# Mezzanine_GPIO_Breakout.net
KiCad netlist of a schematic drawn in EAGLE
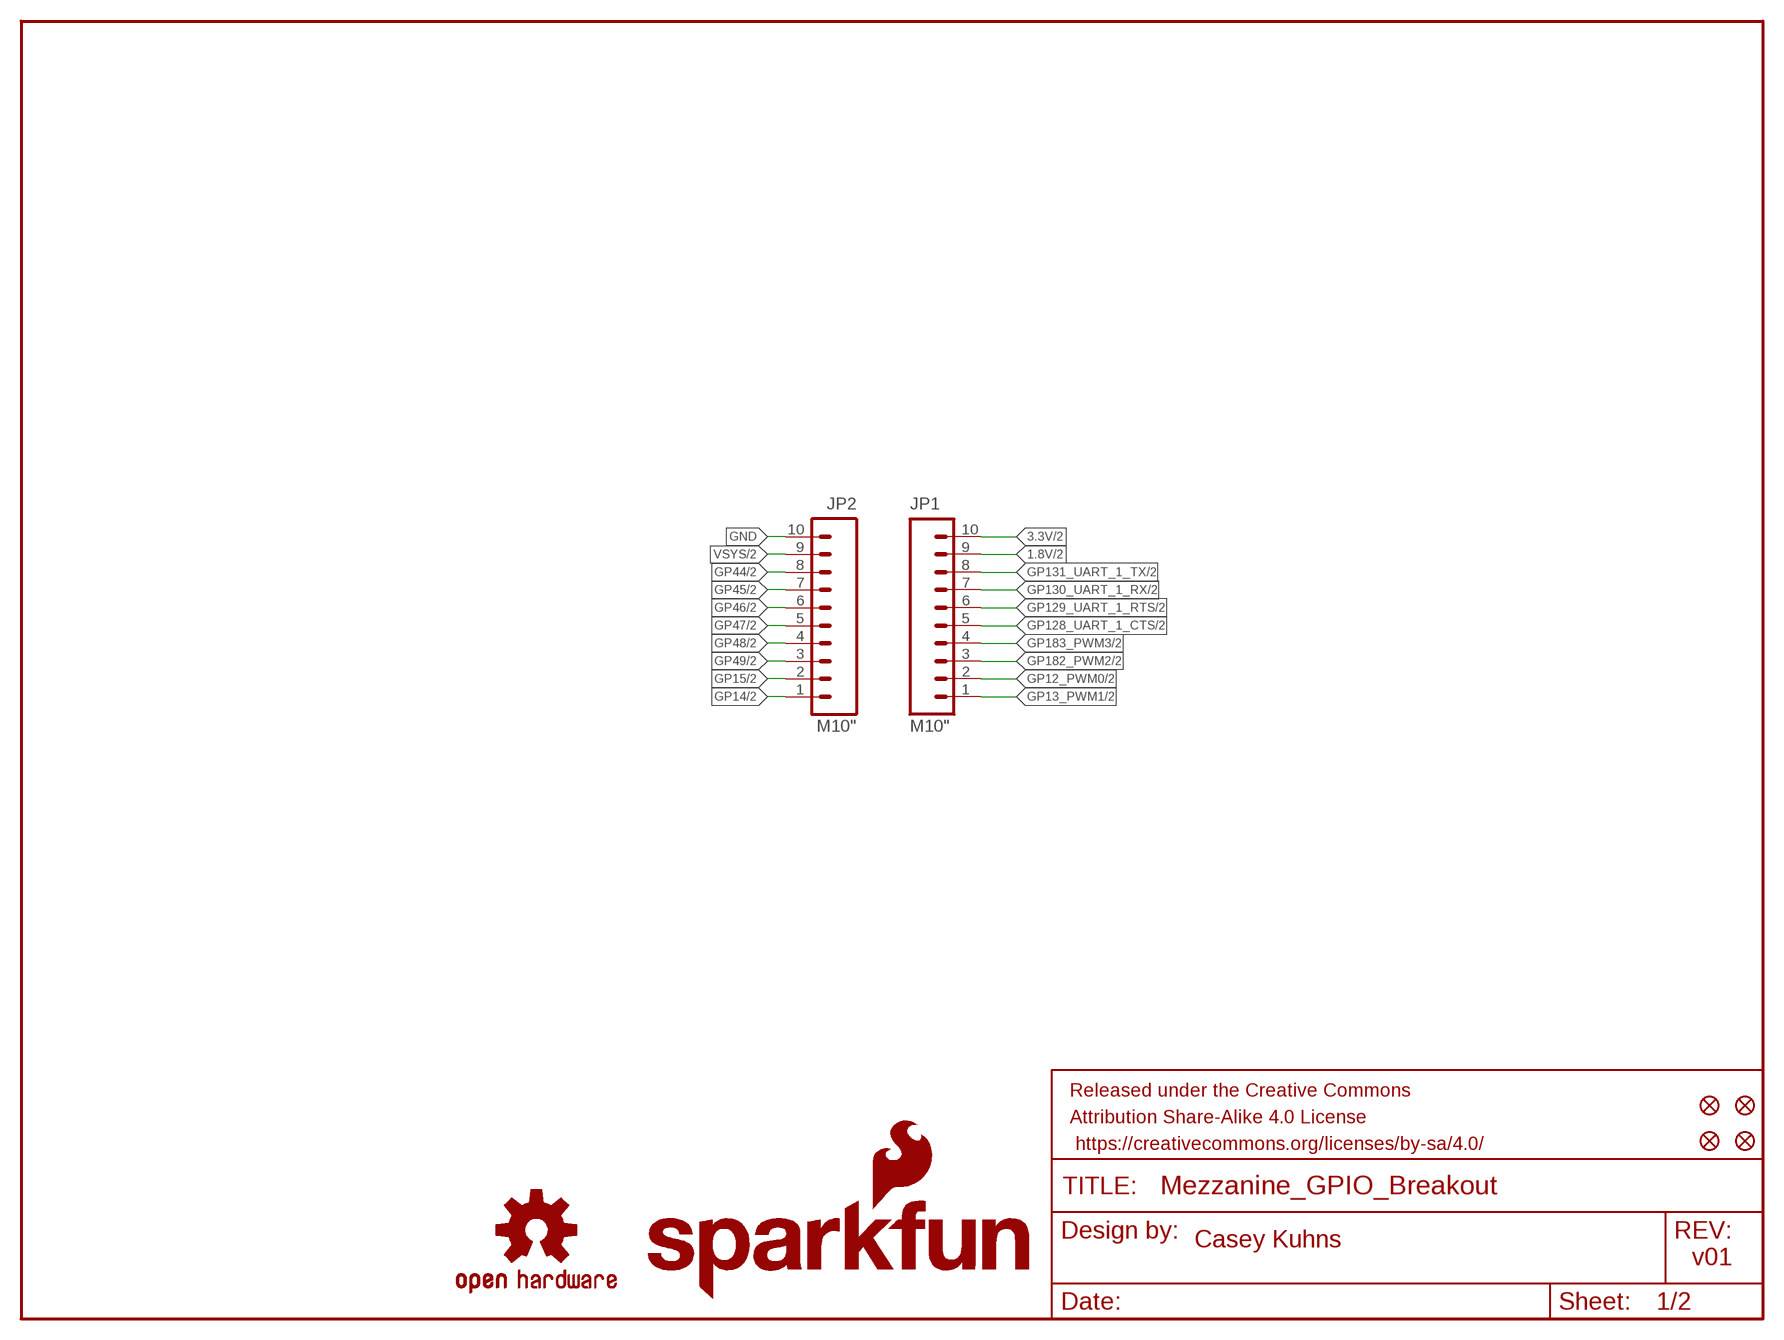
[diagram p0: schematic, sheet 1]
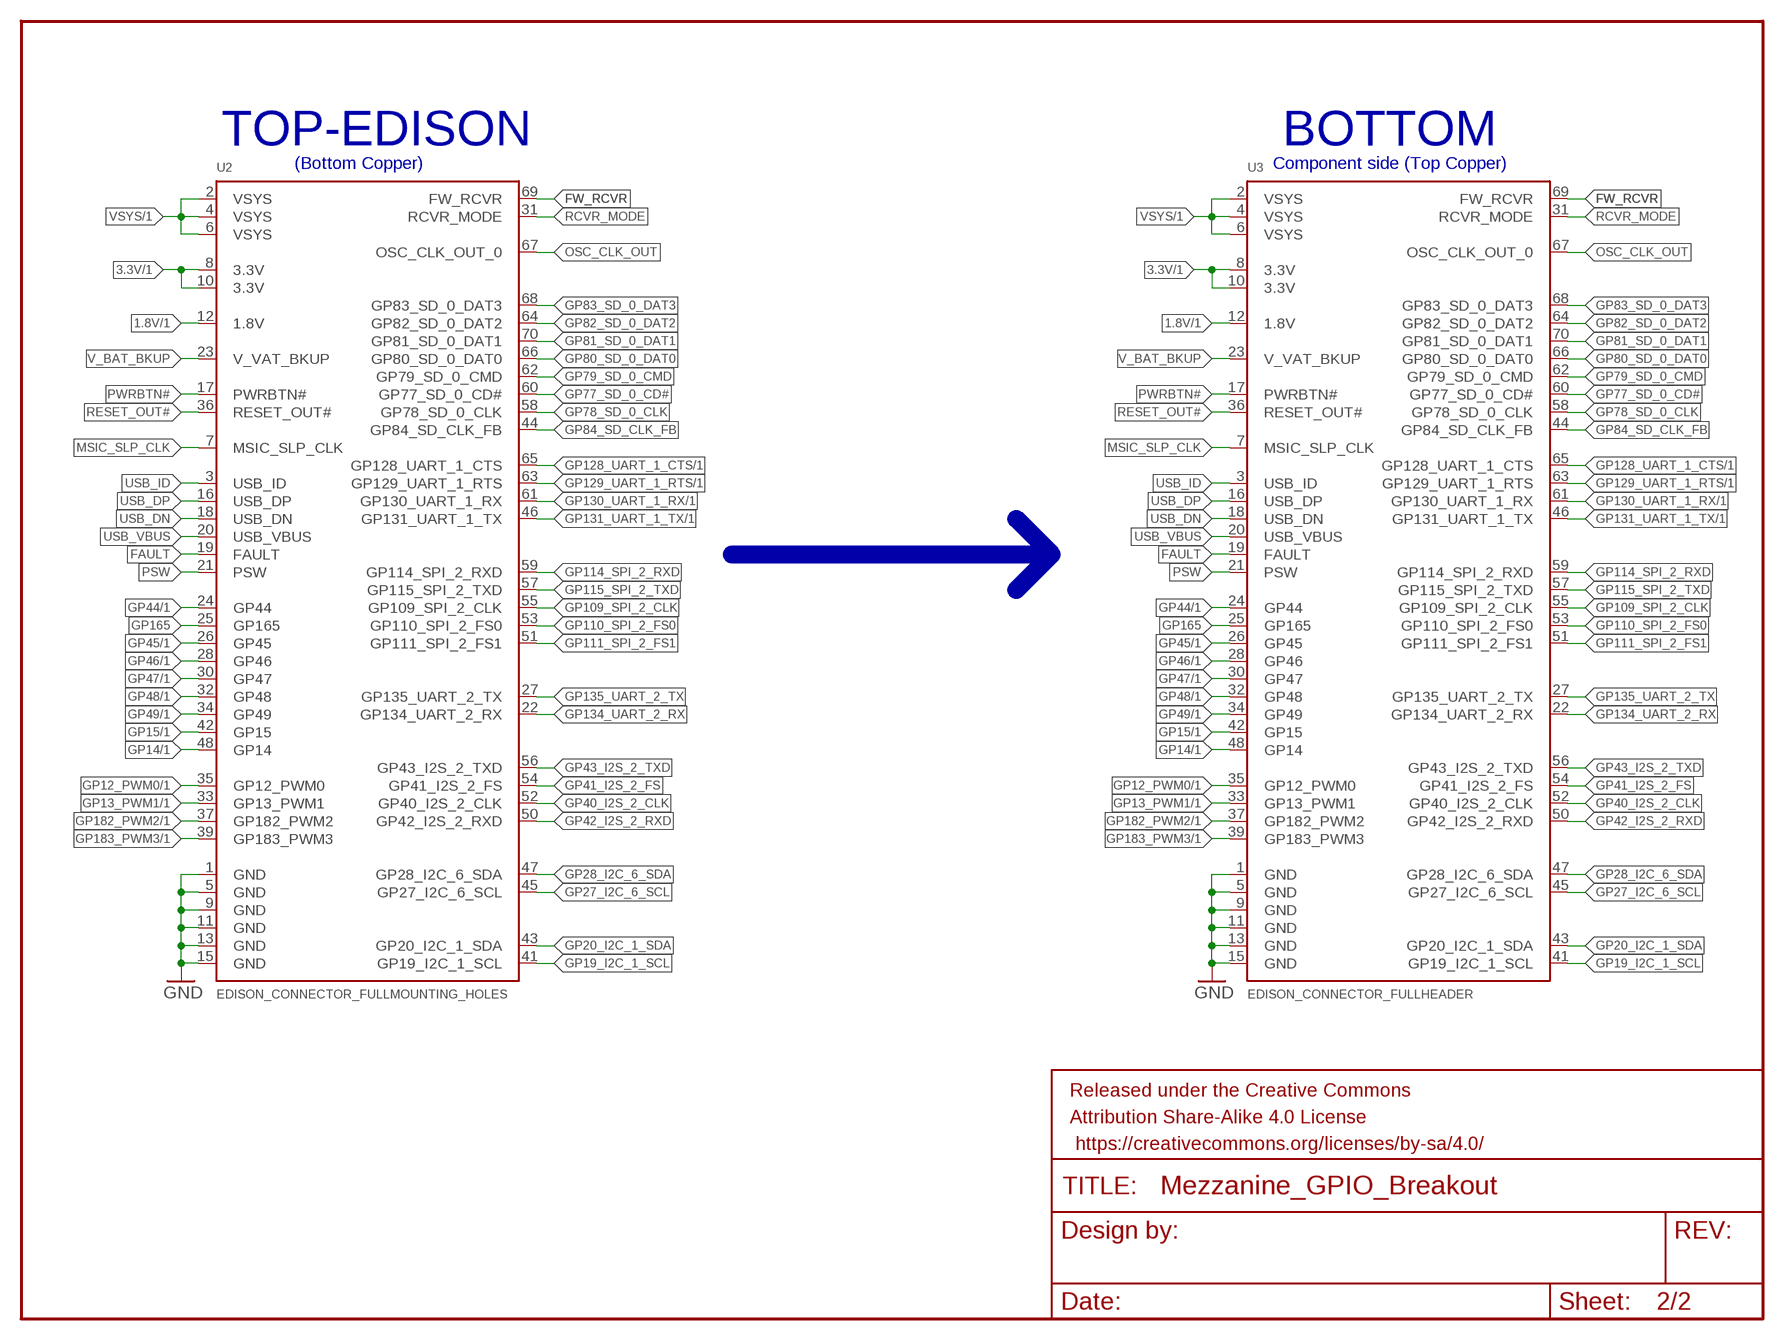
[diagram p1: schematic, sheet 2]

(export (version "E")
  (design (tool "Eeschema 10.0.6"))
  (components
    (comp (ref "FRAME2")
      (value "FRAME-LETTER")
      (footprint "eagle-import:CREATIVE_COMMONS")
      (libsource (lib "eagle-import") (part "FRAME-LETTER"))
    )
    (comp (ref "U2")
      (value "EDISON_CONNECTOR_FULLMOUNTING_HOLES")
      (footprint "eagle-import:EDISON_DAUGHTER")
      (libsource (lib "eagle-import") (part "EDISON_CONNECTOR_FULLMOUNTING_HOLES"))
    )
    (comp (ref "U3")
      (value "EDISON_CONNECTOR_FULLHEADER")
      (footprint "eagle-import:DF40C-70DP-0.4(51)")
      (libsource (lib "eagle-import") (part "EDISON_CONNECTOR_FULLHEADER"))
    )
    (comp (ref "FID1")
      (value "FIDUCIAL1X2")
      (footprint "eagle-import:FIDUCIAL-1X2")
      (libsource (lib "eagle-import") (part "FIDUCIAL1X2"))
    )
    (comp (ref "FID2")
      (value "FIDUCIAL1X2")
      (footprint "eagle-import:FIDUCIAL-1X2")
      (libsource (lib "eagle-import") (part "FIDUCIAL1X2"))
    )
    (comp (ref "FID3")
      (value "FIDUCIAL1X2")
      (footprint "eagle-import:FIDUCIAL-1X2")
      (libsource (lib "eagle-import") (part "FIDUCIAL1X2"))
    )
    (comp (ref "FID4")
      (value "FIDUCIAL1X2")
      (footprint "eagle-import:FIDUCIAL-1X2")
      (libsource (lib "eagle-import") (part "FIDUCIAL1X2"))
    )
    (comp (ref "FRAME1")
      (value "FRAME-LETTER")
      (footprint "eagle-import:CREATIVE_COMMONS")
      (libsource (lib "eagle-import") (part "FRAME-LETTER"))
    )
    (comp (ref "JP1")
      (value "M10\"")
      (footprint "eagle-import:1X10")
      (libsource (lib "eagle-import") (part "M10{dblquote}"))
    )
    (comp (ref "JP2")
      (value "M10\"")
      (footprint "eagle-import:1X10")
      (libsource (lib "eagle-import") (part "M10{dblquote}"))
    )
    (comp (ref "LOGO1")
      (value "OSHW-LOGOS")
      (footprint "eagle-import:OSHW-LOGO-S")
      (libsource (lib "eagle-import") (part "OSHW-LOGOS"))
    )
    (comp (ref "LOGO4")
      (value "SFE_LOGO_NAME_FLAME.1_INCH")
      (footprint "eagle-import:SFE_LOGO_NAME_FLAME_.1")
      (libsource (lib "eagle-import") (part "SFE_LOGO_NAME_FLAME.1_INCH"))
    )
  )
  (nets
    (net (code "1") (name "1.8V") (class "Default")
      (node (ref "JP1") (pin "9") (pinfunction "9_9") (pintype "passive"))
      (node (ref "U2") (pin "12") (pinfunction "1.8V_12") (pintype "bidirectional"))
      (node (ref "U3") (pin "12") (pinfunction "1.8V_12") (pintype "bidirectional"))
    )
    (net (code "2") (name "3.3V") (class "Default")
      (node (ref "JP1") (pin "10") (pinfunction "10_10") (pintype "passive"))
      (node (ref "U2") (pin "10") (pinfunction "3.3V_10") (pintype "bidirectional"))
      (node (ref "U2") (pin "8") (pinfunction "3.3V_8") (pintype "bidirectional"))
      (node (ref "U3") (pin "10") (pinfunction "3.3V_10") (pintype "bidirectional"))
      (node (ref "U3") (pin "8") (pinfunction "3.3V_8") (pintype "bidirectional"))
    )
    (net (code "3") (name "FAULT") (class "Default")
      (node (ref "U2") (pin "19") (pinfunction "FAULT_19") (pintype "bidirectional"))
      (node (ref "U3") (pin "19") (pinfunction "FAULT_19") (pintype "bidirectional"))
    )
    (net (code "4") (name "FW_RCVR") (class "Default")
      (node (ref "U2") (pin "69") (pinfunction "FW_RCVR_69") (pintype "bidirectional"))
      (node (ref "U3") (pin "69") (pinfunction "FW_RCVR_69") (pintype "bidirectional"))
    )
    (net (code "5") (name "GND") (class "Default")
      (node (ref "JP2") (pin "10") (pinfunction "10_10") (pintype "passive"))
      (node (ref "U2") (pin "1") (pinfunction "GND_1") (pintype "bidirectional"))
      (node (ref "U2") (pin "11") (pinfunction "GND_11") (pintype "bidirectional"))
      (node (ref "U2") (pin "13") (pinfunction "GND_13") (pintype "bidirectional"))
      (node (ref "U2") (pin "15") (pinfunction "GND_15") (pintype "bidirectional"))
      (node (ref "U2") (pin "5") (pinfunction "GND_5") (pintype "bidirectional"))
      (node (ref "U2") (pin "9") (pinfunction "GND_9") (pintype "bidirectional"))
      (node (ref "U3") (pin "1") (pinfunction "GND_1") (pintype "bidirectional"))
      (node (ref "U3") (pin "11") (pinfunction "GND_11") (pintype "bidirectional"))
      (node (ref "U3") (pin "13") (pinfunction "GND_13") (pintype "bidirectional"))
      (node (ref "U3") (pin "15") (pinfunction "GND_15") (pintype "bidirectional"))
      (node (ref "U3") (pin "5") (pinfunction "GND_5") (pintype "bidirectional"))
      (node (ref "U3") (pin "9") (pinfunction "GND_9") (pintype "bidirectional"))
    )
    (net (code "6") (name "GP12_PWM0") (class "Default")
      (node (ref "JP1") (pin "2") (pinfunction "2_2") (pintype "passive"))
      (node (ref "U2") (pin "35") (pinfunction "GP12_PWM0_35") (pintype "bidirectional"))
      (node (ref "U3") (pin "35") (pinfunction "GP12_PWM0_35") (pintype "bidirectional"))
    )
    (net (code "7") (name "GP13_PWM1") (class "Default")
      (node (ref "JP1") (pin "1") (pinfunction "1_1") (pintype "passive"))
      (node (ref "U2") (pin "33") (pinfunction "GP13_PWM1_33") (pintype "bidirectional"))
      (node (ref "U3") (pin "33") (pinfunction "GP13_PWM1_33") (pintype "bidirectional"))
    )
    (net (code "8") (name "GP14") (class "Default")
      (node (ref "JP2") (pin "1") (pinfunction "1_1") (pintype "passive"))
      (node (ref "U2") (pin "48") (pinfunction "GP14_48") (pintype "bidirectional"))
      (node (ref "U3") (pin "48") (pinfunction "GP14_48") (pintype "bidirectional"))
    )
    (net (code "9") (name "GP15") (class "Default")
      (node (ref "JP2") (pin "2") (pinfunction "2_2") (pintype "passive"))
      (node (ref "U2") (pin "42") (pinfunction "GP15_42") (pintype "bidirectional"))
      (node (ref "U3") (pin "42") (pinfunction "GP15_42") (pintype "bidirectional"))
    )
    (net (code "10") (name "GP19_I2C_1_SCL") (class "Default")
      (node (ref "U2") (pin "41") (pinfunction "GP19_I2C_1_SCL_41") (pintype "bidirectional"))
      (node (ref "U3") (pin "41") (pinfunction "GP19_I2C_1_SCL_41") (pintype "bidirectional"))
    )
    (net (code "11") (name "GP20_I2C_1_SDA") (class "Default")
      (node (ref "U2") (pin "43") (pinfunction "GP20_I2C_1_SDA_43") (pintype "bidirectional"))
      (node (ref "U3") (pin "43") (pinfunction "GP20_I2C_1_SDA_43") (pintype "bidirectional"))
    )
    (net (code "12") (name "GP27_I2C_6_SCL") (class "Default")
      (node (ref "U2") (pin "45") (pinfunction "GP27_I2C_6_SCL_45") (pintype "bidirectional"))
      (node (ref "U3") (pin "45") (pinfunction "GP27_I2C_6_SCL_45") (pintype "bidirectional"))
    )
    (net (code "13") (name "GP28_I2C_6_SDA") (class "Default")
      (node (ref "U2") (pin "47") (pinfunction "GP28_I2C_6_SDA_47") (pintype "bidirectional"))
      (node (ref "U3") (pin "47") (pinfunction "GP28_I2C_6_SDA_47") (pintype "bidirectional"))
    )
    (net (code "14") (name "GP40_I2S_2_CLK") (class "Default")
      (node (ref "U2") (pin "52") (pinfunction "GP40_I2S_2_CLK_52") (pintype "bidirectional"))
      (node (ref "U3") (pin "52") (pinfunction "GP40_I2S_2_CLK_52") (pintype "bidirectional"))
    )
    (net (code "15") (name "GP41_I2S_2_FS") (class "Default")
      (node (ref "U2") (pin "54") (pinfunction "GP41_I2S_2_FS_54") (pintype "bidirectional"))
      (node (ref "U3") (pin "54") (pinfunction "GP41_I2S_2_FS_54") (pintype "bidirectional"))
    )
    (net (code "16") (name "GP42_I2S_2_RXD") (class "Default")
      (node (ref "U2") (pin "50") (pinfunction "GP42_I2S_2_RXD_50") (pintype "bidirectional"))
      (node (ref "U3") (pin "50") (pinfunction "GP42_I2S_2_RXD_50") (pintype "bidirectional"))
    )
    (net (code "17") (name "GP43_I2S_2_TXD") (class "Default")
      (node (ref "U2") (pin "56") (pinfunction "GP43_I2S_2_TXD_56") (pintype "bidirectional"))
      (node (ref "U3") (pin "56") (pinfunction "GP43_I2S_2_TXD_56") (pintype "bidirectional"))
    )
    (net (code "18") (name "GP44") (class "Default")
      (node (ref "JP2") (pin "8") (pinfunction "8_8") (pintype "passive"))
      (node (ref "U2") (pin "24") (pinfunction "GP44_24") (pintype "bidirectional"))
      (node (ref "U3") (pin "24") (pinfunction "GP44_24") (pintype "bidirectional"))
    )
    (net (code "19") (name "GP45") (class "Default")
      (node (ref "JP2") (pin "7") (pinfunction "7_7") (pintype "passive"))
      (node (ref "U2") (pin "26") (pinfunction "GP45_26") (pintype "bidirectional"))
      (node (ref "U3") (pin "26") (pinfunction "GP45_26") (pintype "bidirectional"))
    )
    (net (code "20") (name "GP46") (class "Default")
      (node (ref "JP2") (pin "6") (pinfunction "6_6") (pintype "passive"))
      (node (ref "U2") (pin "28") (pinfunction "GP46_28") (pintype "bidirectional"))
      (node (ref "U3") (pin "28") (pinfunction "GP46_28") (pintype "bidirectional"))
    )
    (net (code "21") (name "GP47") (class "Default")
      (node (ref "JP2") (pin "5") (pinfunction "5_5") (pintype "passive"))
      (node (ref "U2") (pin "30") (pinfunction "GP47_30") (pintype "bidirectional"))
      (node (ref "U3") (pin "30") (pinfunction "GP47_30") (pintype "bidirectional"))
    )
    (net (code "22") (name "GP48") (class "Default")
      (node (ref "JP2") (pin "4") (pinfunction "4_4") (pintype "passive"))
      (node (ref "U2") (pin "32") (pinfunction "GP48_32") (pintype "bidirectional"))
      (node (ref "U3") (pin "32") (pinfunction "GP48_32") (pintype "bidirectional"))
    )
    (net (code "23") (name "GP49") (class "Default")
      (node (ref "JP2") (pin "3") (pinfunction "3_3") (pintype "passive"))
      (node (ref "U2") (pin "34") (pinfunction "GP49_34") (pintype "bidirectional"))
      (node (ref "U3") (pin "34") (pinfunction "GP49_34") (pintype "bidirectional"))
    )
    (net (code "24") (name "GP77_SD_0_CD#") (class "Default")
      (node (ref "U2") (pin "60") (pinfunction "GP77_SD_0_CD#_60") (pintype "bidirectional"))
      (node (ref "U3") (pin "60") (pinfunction "GP77_SD_0_CD#_60") (pintype "bidirectional"))
    )
    (net (code "25") (name "GP78_SD_0_CLK") (class "Default")
      (node (ref "U2") (pin "58") (pinfunction "GP78_SD_0_CLK_58") (pintype "bidirectional"))
      (node (ref "U3") (pin "58") (pinfunction "GP78_SD_0_CLK_58") (pintype "bidirectional"))
    )
    (net (code "26") (name "GP79_SD_0_CMD") (class "Default")
      (node (ref "U2") (pin "62") (pinfunction "GP79_SD_0_CMD_62") (pintype "bidirectional"))
      (node (ref "U3") (pin "62") (pinfunction "GP79_SD_0_CMD_62") (pintype "bidirectional"))
    )
    (net (code "27") (name "GP80_SD_0_DAT0") (class "Default")
      (node (ref "U2") (pin "66") (pinfunction "GP80_SD_0_DAT0_66") (pintype "bidirectional"))
      (node (ref "U3") (pin "66") (pinfunction "GP80_SD_0_DAT0_66") (pintype "bidirectional"))
    )
    (net (code "28") (name "GP81_SD_0_DAT1") (class "Default")
      (node (ref "U2") (pin "70") (pinfunction "GP81_SD_0_DAT1_70") (pintype "bidirectional"))
      (node (ref "U3") (pin "70") (pinfunction "GP81_SD_0_DAT1_70") (pintype "bidirectional"))
    )
    (net (code "29") (name "GP82_SD_0_DAT2") (class "Default")
      (node (ref "U2") (pin "64") (pinfunction "GP82_SD_0_DAT2_64") (pintype "bidirectional"))
      (node (ref "U3") (pin "64") (pinfunction "GP82_SD_0_DAT2_64") (pintype "bidirectional"))
    )
    (net (code "30") (name "GP83_SD_0_DAT3") (class "Default")
      (node (ref "U2") (pin "68") (pinfunction "GP83_SD_0_DAT3_68") (pintype "bidirectional"))
      (node (ref "U3") (pin "68") (pinfunction "GP83_SD_0_DAT3_68") (pintype "bidirectional"))
    )
    (net (code "31") (name "GP84_SD_CLK_FB") (class "Default")
      (node (ref "U2") (pin "44") (pinfunction "GP84_SD_CLK_FB_44") (pintype "bidirectional"))
      (node (ref "U3") (pin "44") (pinfunction "GP84_SD_CLK_FB_44") (pintype "bidirectional"))
    )
    (net (code "32") (name "GP109_SPI_2_CLK") (class "Default")
      (node (ref "U2") (pin "55") (pinfunction "GP109_SPI_2_CLK_55") (pintype "bidirectional"))
      (node (ref "U3") (pin "55") (pinfunction "GP109_SPI_2_CLK_55") (pintype "bidirectional"))
    )
    (net (code "33") (name "GP110_SPI_2_FS0") (class "Default")
      (node (ref "U2") (pin "53") (pinfunction "GP110_SPI_2_FS0_53") (pintype "bidirectional"))
      (node (ref "U3") (pin "53") (pinfunction "GP110_SPI_2_FS0_53") (pintype "bidirectional"))
    )
    (net (code "34") (name "GP111_SPI_2_FS1") (class "Default")
      (node (ref "U2") (pin "51") (pinfunction "GP111_SPI_2_FS1_51") (pintype "bidirectional"))
      (node (ref "U3") (pin "51") (pinfunction "GP111_SPI_2_FS1_51") (pintype "bidirectional"))
    )
    (net (code "35") (name "GP114_SPI_2_RXD") (class "Default")
      (node (ref "U2") (pin "59") (pinfunction "GP114_SPI_2_RXD_59") (pintype "bidirectional"))
      (node (ref "U3") (pin "59") (pinfunction "GP114_SPI_2_RXD_59") (pintype "bidirectional"))
    )
    (net (code "36") (name "GP115_SPI_2_TXD") (class "Default")
      (node (ref "U2") (pin "57") (pinfunction "GP115_SPI_2_TXD_57") (pintype "bidirectional"))
      (node (ref "U3") (pin "57") (pinfunction "GP115_SPI_2_TXD_57") (pintype "bidirectional"))
    )
    (net (code "37") (name "GP128_UART_1_CTS") (class "Default")
      (node (ref "JP1") (pin "5") (pinfunction "5_5") (pintype "passive"))
      (node (ref "U2") (pin "65") (pinfunction "GP128_UART_1_CTS_65") (pintype "bidirectional"))
      (node (ref "U3") (pin "65") (pinfunction "GP128_UART_1_CTS_65") (pintype "bidirectional"))
    )
    (net (code "38") (name "GP129_UART_1_RTS") (class "Default")
      (node (ref "JP1") (pin "6") (pinfunction "6_6") (pintype "passive"))
      (node (ref "U2") (pin "63") (pinfunction "GP129_UART_1_RTS_63") (pintype "bidirectional"))
      (node (ref "U3") (pin "63") (pinfunction "GP129_UART_1_RTS_63") (pintype "bidirectional"))
    )
    (net (code "39") (name "GP130_UART_1_RX") (class "Default")
      (node (ref "JP1") (pin "7") (pinfunction "7_7") (pintype "passive"))
      (node (ref "U2") (pin "61") (pinfunction "GP130_UART_1_RX_61") (pintype "bidirectional"))
      (node (ref "U3") (pin "61") (pinfunction "GP130_UART_1_RX_61") (pintype "bidirectional"))
    )
    (net (code "40") (name "GP131_UART_1_TX") (class "Default")
      (node (ref "JP1") (pin "8") (pinfunction "8_8") (pintype "passive"))
      (node (ref "U2") (pin "46") (pinfunction "GP131_UART_1_TX_46") (pintype "bidirectional"))
      (node (ref "U3") (pin "46") (pinfunction "GP131_UART_1_TX_46") (pintype "bidirectional"))
    )
    (net (code "41") (name "GP134_UART_2_RX") (class "Default")
      (node (ref "U2") (pin "22") (pinfunction "GP134_UART_2_RX_22") (pintype "bidirectional"))
      (node (ref "U3") (pin "22") (pinfunction "GP134_UART_2_RX_22") (pintype "bidirectional"))
    )
    (net (code "42") (name "GP135_UART_2_TX") (class "Default")
      (node (ref "U2") (pin "27") (pinfunction "GP135_UART_2_TX_27") (pintype "bidirectional"))
      (node (ref "U3") (pin "27") (pinfunction "GP135_UART_2_TX_27") (pintype "bidirectional"))
    )
    (net (code "43") (name "GP165") (class "Default")
      (node (ref "U2") (pin "25") (pinfunction "GP165_25") (pintype "bidirectional"))
      (node (ref "U3") (pin "25") (pinfunction "GP165_25") (pintype "bidirectional"))
    )
    (net (code "44") (name "GP182_PWM2") (class "Default")
      (node (ref "JP1") (pin "3") (pinfunction "3_3") (pintype "passive"))
      (node (ref "U2") (pin "37") (pinfunction "GP182_PWM2_37") (pintype "bidirectional"))
      (node (ref "U3") (pin "37") (pinfunction "GP182_PWM2_37") (pintype "bidirectional"))
    )
    (net (code "45") (name "GP183_PWM3") (class "Default")
      (node (ref "JP1") (pin "4") (pinfunction "4_4") (pintype "passive"))
      (node (ref "U2") (pin "39") (pinfunction "GP183_PWM3_39") (pintype "bidirectional"))
      (node (ref "U3") (pin "39") (pinfunction "GP183_PWM3_39") (pintype "bidirectional"))
    )
    (net (code "46") (name "MSIC_SLP_CLK") (class "Default")
      (node (ref "U2") (pin "7") (pinfunction "MSIC_SLP_CLK_7") (pintype "bidirectional"))
      (node (ref "U3") (pin "7") (pinfunction "MSIC_SLP_CLK_7") (pintype "bidirectional"))
    )
    (net (code "47") (name "OSC_CLK_OUT") (class "Default")
      (node (ref "U2") (pin "67") (pinfunction "OSC_CLK_OUT_0_67") (pintype "bidirectional"))
      (node (ref "U3") (pin "67") (pinfunction "OSC_CLK_OUT_0_67") (pintype "bidirectional"))
    )
    (net (code "48") (name "PSW") (class "Default")
      (node (ref "U2") (pin "21") (pinfunction "PSW_21") (pintype "bidirectional"))
      (node (ref "U3") (pin "21") (pinfunction "PSW_21") (pintype "bidirectional"))
    )
    (net (code "49") (name "PWRBTN#") (class "Default")
      (node (ref "U2") (pin "17") (pinfunction "PWRBTN#_17") (pintype "bidirectional"))
      (node (ref "U3") (pin "17") (pinfunction "PWRBTN#_17") (pintype "bidirectional"))
    )
    (net (code "50") (name "RCVR_MODE") (class "Default")
      (node (ref "U2") (pin "31") (pinfunction "RCVR_MODE_31") (pintype "bidirectional"))
      (node (ref "U3") (pin "31") (pinfunction "RCVR_MODE_31") (pintype "bidirectional"))
    )
    (net (code "51") (name "RESET_OUT#") (class "Default")
      (node (ref "U2") (pin "36") (pinfunction "RESET_OUT#_36") (pintype "bidirectional"))
      (node (ref "U3") (pin "36") (pinfunction "RESET_OUT#_36") (pintype "bidirectional"))
    )
    (net (code "52") (name "USB_DN") (class "Default")
      (node (ref "U2") (pin "18") (pinfunction "USB_DN_18") (pintype "bidirectional"))
      (node (ref "U3") (pin "18") (pinfunction "USB_DN_18") (pintype "bidirectional"))
    )
    (net (code "53") (name "USB_DP") (class "Default")
      (node (ref "U2") (pin "16") (pinfunction "USB_DP_16") (pintype "bidirectional"))
      (node (ref "U3") (pin "16") (pinfunction "USB_DP_16") (pintype "bidirectional"))
    )
    (net (code "54") (name "USB_ID") (class "Default")
      (node (ref "U2") (pin "3") (pinfunction "USB_ID_3") (pintype "bidirectional"))
      (node (ref "U3") (pin "3") (pinfunction "USB_ID_3") (pintype "bidirectional"))
    )
    (net (code "55") (name "USB_VBUS") (class "Default")
      (node (ref "U2") (pin "20") (pinfunction "USB_VBUS_20") (pintype "bidirectional"))
      (node (ref "U3") (pin "20") (pinfunction "USB_VBUS_20") (pintype "bidirectional"))
    )
    (net (code "56") (name "VSYS") (class "Default")
      (node (ref "JP2") (pin "9") (pinfunction "9_9") (pintype "passive"))
      (node (ref "U2") (pin "2") (pinfunction "VSYS_2") (pintype "bidirectional"))
      (node (ref "U2") (pin "4") (pinfunction "VSYS_4") (pintype "bidirectional"))
      (node (ref "U2") (pin "6") (pinfunction "VSYS_6") (pintype "bidirectional"))
      (node (ref "U3") (pin "2") (pinfunction "VSYS_2") (pintype "bidirectional"))
      (node (ref "U3") (pin "4") (pinfunction "VSYS_4") (pintype "bidirectional"))
      (node (ref "U3") (pin "6") (pinfunction "VSYS_6") (pintype "bidirectional"))
    )
    (net (code "57") (name "V_BAT_BKUP") (class "Default")
      (node (ref "U2") (pin "23") (pinfunction "V_VAT_BKUP_23") (pintype "bidirectional"))
      (node (ref "U3") (pin "23") (pinfunction "V_VAT_BKUP_23") (pintype "bidirectional"))
    )
  )
)
